# DRV8711EVM.net
KiCad netlist of a schematic drawn in Altium Designer
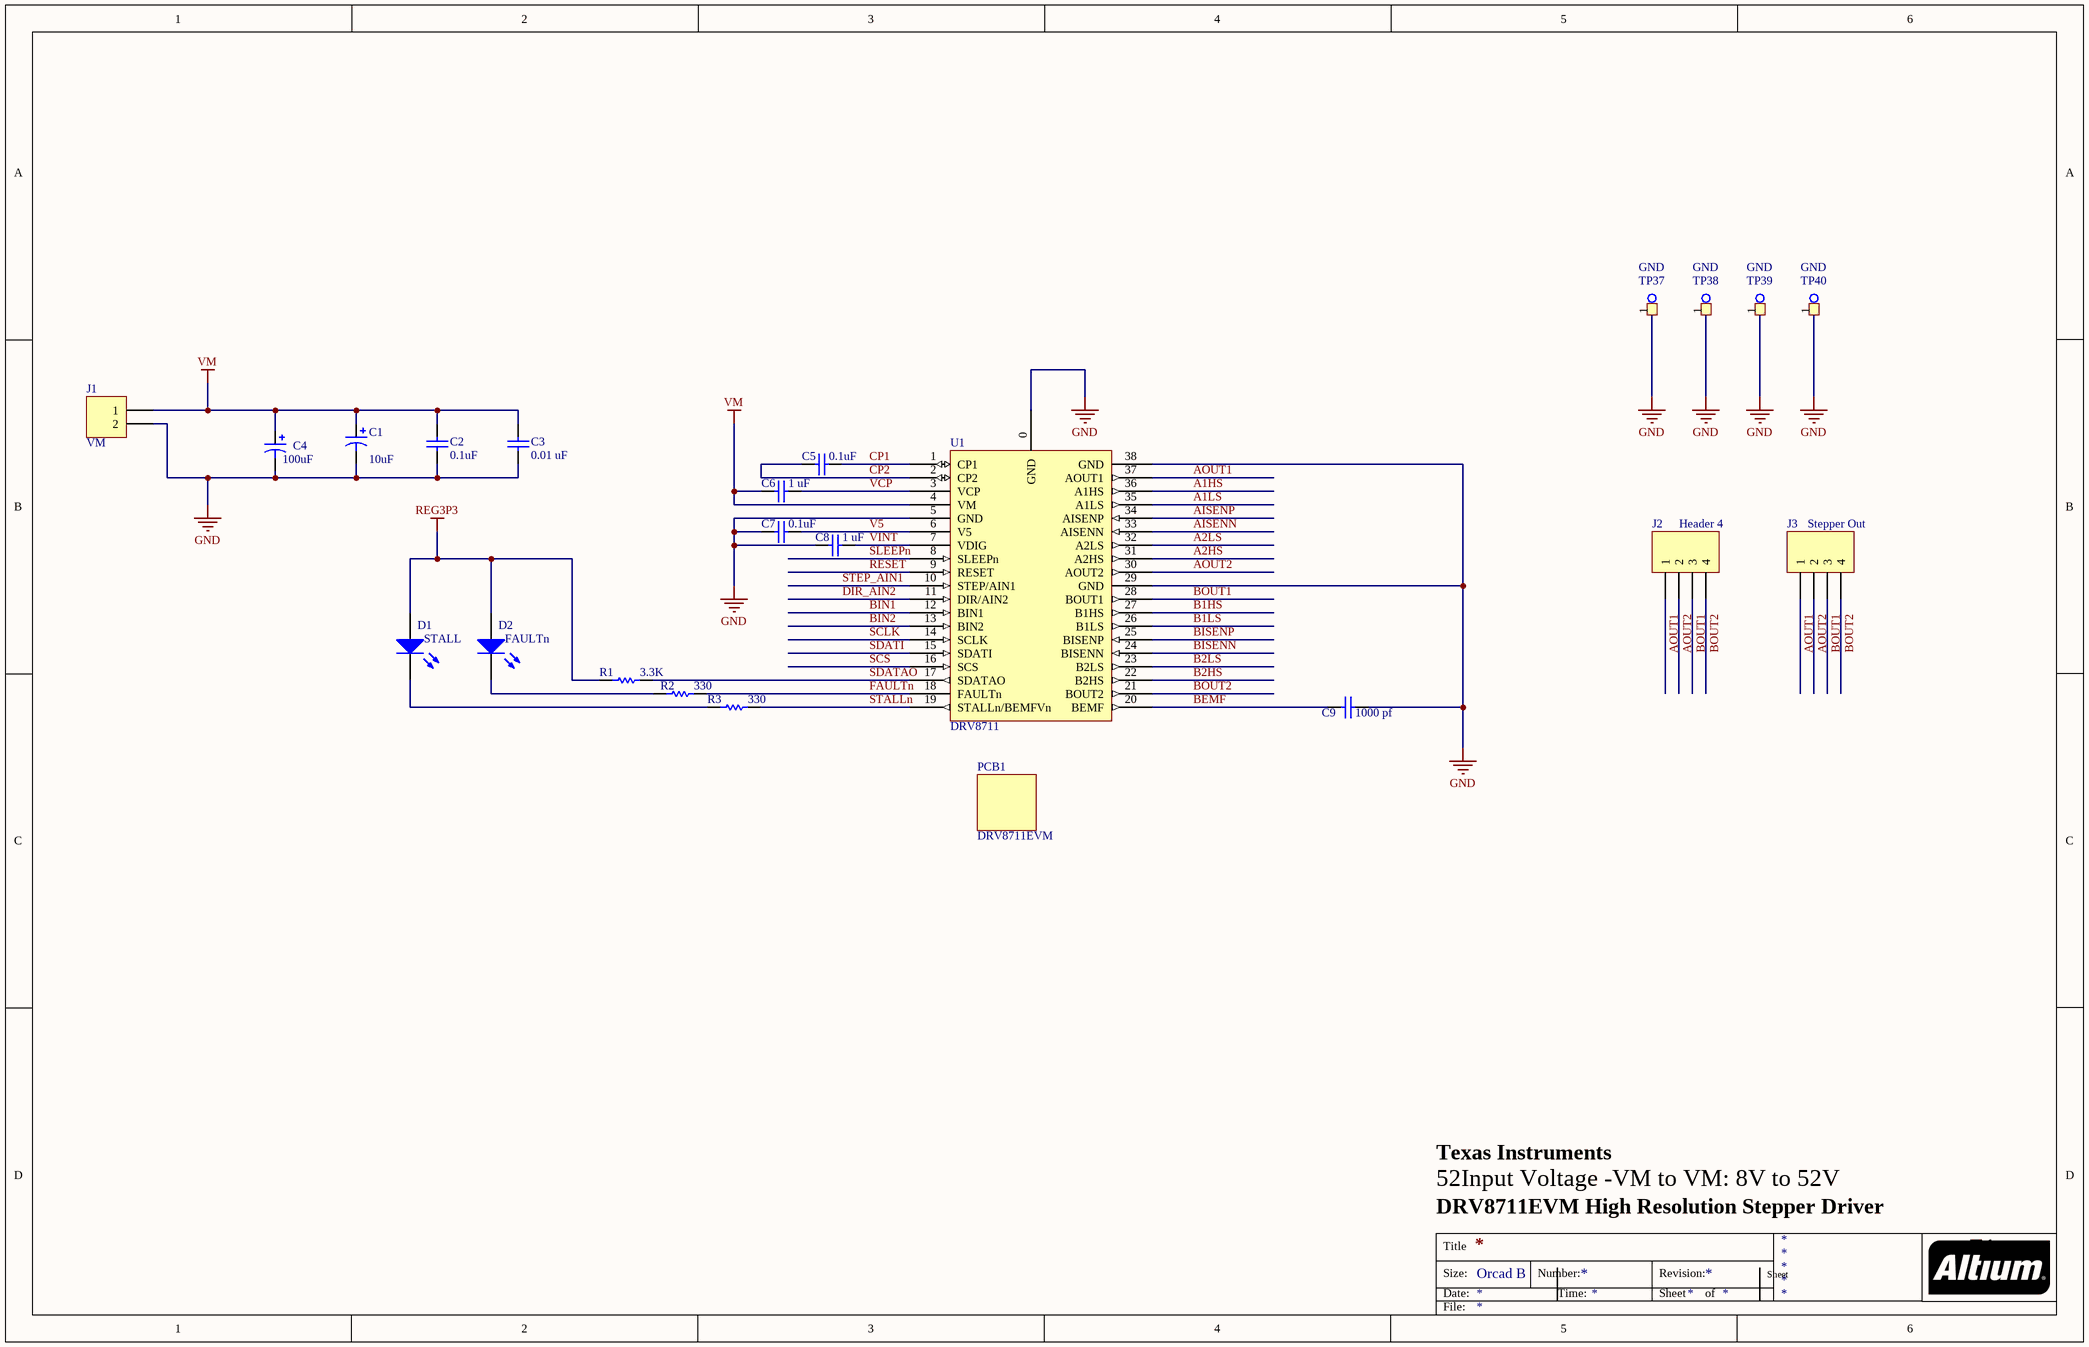
[diagram p0: DRV8711EVM.SchDoc]

(export (version "E")
  (design (tool "Eeschema 10.0.6"))
  (components
    (comp (ref "C1")
      (value "10uF")
      (footprint "RB .1/.250 - SML")
      (description "CAP ALUM 10UF 25V 20% RADIAL")
      (fields (field (name "MFG PART NUMBER") "UVR1E100MDD") (field (name "MANUFACTURER") "Nichicon"))
      (libsource (lib "Miscellaneous Devices") (part "Cap Pol1"))
    )
    (comp (ref "C2")
      (value "0.1uF")
      (footprint "0603-SMT")
      (description "Capacitor")
      (fields (field (name "MANUFACTURER") "TDK") (field (name "MFG PART NUMBER") "C1608X7S2A104M"))
      (libsource (lib "Miscellaneous Devices") (part "Cap"))
    )
    (comp (ref "C3")
      (value "0.01 uF")
      (footprint "0603-SMT")
      (description "Capacitor")
      (fields (field (name "MANUFACTURER") "TDK") (field (name "MFG PART NUMBER") "C1608X7R2A103K"))
      (libsource (lib "Miscellaneous Devices") (part "Cap"))
    )
    (comp (ref "C4")
      (value "100uF")
      (footprint "RB 5.0mm/12.5mm_NoPost")
      (description "CAP ALUM 100UF 100V 20% RADIAL")
      (fields (field (name "MFG PART NUMBER") "ECA-2AM101") (field (name "MANUFACTURER") "Panasonic"))
      (libsource (lib "Miscellaneous Devices") (part "Cap Pol1"))
    )
    (comp (ref "C5")
      (value "0.1uF")
      (footprint "0603-SMT")
      (description "Capacitor")
      (fields (field (name "MANUFACTURER") "TDK") (field (name "MFG PART NUMBER") "C1608X7S2A104M"))
      (libsource (lib "Miscellaneous Devices") (part "Cap"))
    )
    (comp (ref "C6")
      (value "1 uF")
      (footprint "1206")
      (description "Capacitor")
      (fields (field (name "MANUFACTURER") "TDK") (field (name "MFG PART NUMBER") "C3216X7R1H105K"))
      (libsource (lib "Miscellaneous Devices") (part "Cap"))
    )
    (comp (ref "C7")
      (value "0.1uF")
      (footprint "0603-SMT")
      (description "Capacitor")
      (fields (field (name "MANUFACTURER") "Yageo") (field (name "MFG PART NUMBER") "CC0603ZRY5V9BB104"))
      (libsource (lib "Miscellaneous Devices") (part "Cap"))
    )
    (comp (ref "C8")
      (value "1 uF")
      (footprint "0603-SMT")
      (description "Capacitor")
      (fields (field (name "MANUFACTURER") "TDK") (field (name "MFG PART NUMBER") "C1608Y5V1A105Z"))
      (libsource (lib "Miscellaneous Devices") (part "Cap"))
    )
    (comp (ref "C9")
      (value "1000 pf")
      (footprint "0603-SMT")
      (description "Capacitor")
      (fields (field (name "MANUFACTURER") "Yageo") (field (name "MFG PART NUMBER") "CC0603JRNPO8BN102"))
      (libsource (lib "Miscellaneous Devices") (part "Cap"))
    )
    (comp (ref "D1")
      (value "STALL")
      (footprint "1206_LED")
      (description "LED RED FACE UP 1206")
      (fields (field (name "DK PART NUMBER") "P11532CT-ND") (field (name "MANUFACTURER") "Panasonic"))
      (libsource (lib "Miscellaneous Devices") (part "LED2"))
    )
    (comp (ref "D2")
      (value "FAULTn")
      (footprint "1206_LED")
      (description "LED RED FACE UP 1206")
      (fields (field (name "DK PART NUMBER") "P11532CT-ND") (field (name "MANUFACTURER") "Panasonic"))
      (libsource (lib "Miscellaneous Devices") (part "LED2"))
    )
    (comp (ref "J1")
      (value "VM")
      (footprint "PWR_CONN2")
      (description "TERM BLOCK 5.08MM VERT 2POS PCB")
      (fields
        (field (name "MANUFACTURER") "On Shore Technologies")
        (field (name "MFG PART NUMBER") "OSTTA024163")
      )
      (libsource (lib "Miscellaneous Connectors") (part "Header 2"))
    )
    (comp (ref "J2")
      (value "Header 4")
      (footprint "PWR_CONN4")
      (description "TERM BLOCK 5.08MM VERT 4POS PCB")
      (fields
        (field (name "MANUFACTURER") "On Shore Technologies")
        (field (name "MFG PART NUMBER") "OSTTA044163")
      )
      (libsource (lib "Miscellaneous Connectors") (part "Header 4"))
    )
    (comp (ref "J3")
      (value "Stepper Out")
      (footprint "HDR1X4")
      (description "CONN HEADER .100 SNGL STR 4POS")
      (fields (field (name "DK PART NUMBER") "929647-09-04-ND") (field (name "MANUFACTURER") "3M"))
      (libsource (lib "Miscellaneous Connectors") (part "Header 4"))
    )
    (comp (ref "PCB1")
      (value "DRV8711EVM")
      (footprint "TI_LOGO")
      (description "Bare Board")
      (fields (field (name "DK PART NUMBER") "Board"))
      (libsource (lib "JIQLIB") (part "TI_LOGO"))
    )
    (comp (ref "R1")
      (value "3.3K")
      (footprint "0603-SMT")
      (description "RES 3.3K OHM 1/10W 5% 0603 SMD")
      (fields (field (name "MANUFACTURER") "Panasonic") (field (name "MFG PART NUMBER") "ERJ-3GEYJ332V"))
      (libsource (lib "Zerosen_Small") (part "Res1"))
    )
    (comp (ref "R2")
      (value "330")
      (footprint "0603-SMT")
      (description "Resistor")
      (fields (field (name "MFG PART NUMBER") "RC0603JR-07330RL") (field (name "MANUFACTURER") "Yageo"))
      (libsource (lib "Miscellaneous Devices") (part "Res1"))
    )
    (comp (ref "R3")
      (value "330")
      (footprint "0603-SMT")
      (description "Resistor")
      (fields (field (name "MFG PART NUMBER") "RC0603JR-07330RL") (field (name "MANUFACTURER") "Yageo"))
      (libsource (lib "Miscellaneous Devices") (part "Res1"))
    )
    (comp (ref "TP37")
      (value "GND")
      (footprint "TEST POINT 0.052")
      (description "TEST POINT PC COMPACT .063\"D BLK")
      (fields (field (name "MANUFACTURER") "Keystone") (field (name "MFG PART NUMBER") "5006"))
      (libsource (lib "JIQLIB") (part "TEST POINT"))
    )
    (comp (ref "TP38")
      (value "GND")
      (footprint "TEST POINT 0.052")
      (description "TEST POINT PC COMPACT .063\"D BLK")
      (fields (field (name "MANUFACTURER") "Keystone") (field (name "MFG PART NUMBER") "5006"))
      (libsource (lib "JIQLIB") (part "TEST POINT"))
    )
    (comp (ref "TP39")
      (value "GND")
      (footprint "TEST POINT 0.052")
      (description "TEST POINT PC COMPACT .063\"D BLK")
      (fields (field (name "MANUFACTURER") "Keystone") (field (name "MFG PART NUMBER") "5006"))
      (libsource (lib "JIQLIB") (part "TEST POINT"))
    )
    (comp (ref "TP40")
      (value "GND")
      (footprint "TEST POINT 0.052")
      (description "TEST POINT PC COMPACT .063\"D BLK")
      (fields (field (name "MANUFACTURER") "Keystone") (field (name "MFG PART NUMBER") "5006"))
      (libsource (lib "JIQLIB") (part "TEST POINT"))
    )
    (comp (ref "U1")
      (value "DRV8711")
      (footprint "DCP38 SMT")
      (description "Pre Driver Stepper Motor Controller")
      (fields (field (name "MANUFACTURER") "Texas Instruments") (field (name "MFG PART NUMBER") "DRV8711DCP"))
      (libsource (lib "JIQLIB") (part "DRV8711"))
    )
  )
  (nets
    (net (code "1") (name "/A1HS") (class "Default")
      (node (ref "U1") (pin "36") (pinfunction "A1HS_36") (pintype "output"))
    )
    (net (code "2") (name "/A1LS") (class "Default")
      (node (ref "U1") (pin "35") (pinfunction "A1LS_35") (pintype "output"))
    )
    (net (code "3") (name "/A2HS") (class "Default")
      (node (ref "U1") (pin "31") (pinfunction "A2HS_31") (pintype "output"))
    )
    (net (code "4") (name "/A2LS") (class "Default")
      (node (ref "U1") (pin "32") (pinfunction "A2LS_32") (pintype "output"))
    )
    (net (code "5") (name "/AISENN") (class "Default")
      (node (ref "U1") (pin "33") (pinfunction "AISENN_33") (pintype "input"))
    )
    (net (code "6") (name "/AISENP") (class "Default")
      (node (ref "U1") (pin "34") (pinfunction "AISENP_34") (pintype "input"))
    )
    (net (code "7") (name "/AOUT1") (class "Default")
      (node (ref "J2") (pin "1") (pinfunction "1_1") (pintype "passive"))
      (node (ref "J3") (pin "1") (pinfunction "1_1") (pintype "passive"))
      (node (ref "U1") (pin "37") (pinfunction "AOUT1_37") (pintype "output"))
    )
    (net (code "8") (name "/AOUT2") (class "Default")
      (node (ref "J2") (pin "2") (pinfunction "2_2") (pintype "passive"))
      (node (ref "J3") (pin "2") (pinfunction "2_2") (pintype "passive"))
      (node (ref "U1") (pin "30") (pinfunction "AOUT2_30") (pintype "output"))
    )
    (net (code "9") (name "/B1HS") (class "Default")
      (node (ref "U1") (pin "27") (pinfunction "B1HS_27") (pintype "output"))
    )
    (net (code "10") (name "/B1LS") (class "Default")
      (node (ref "U1") (pin "26") (pinfunction "B1LS_26") (pintype "output"))
    )
    (net (code "11") (name "/B2HS") (class "Default")
      (node (ref "U1") (pin "22") (pinfunction "B2HS_22") (pintype "output"))
    )
    (net (code "12") (name "/B2LS") (class "Default")
      (node (ref "U1") (pin "23") (pinfunction "B2LS_23") (pintype "output"))
    )
    (net (code "13") (name "/BEMF") (class "Default")
      (node (ref "C9") (pin "1") (pinfunction "1_1") (pintype "passive"))
      (node (ref "U1") (pin "20") (pinfunction "BEMF_20") (pintype "output"))
    )
    (net (code "14") (name "/BIN1") (class "Default")
      (node (ref "U1") (pin "12") (pinfunction "BIN1_12") (pintype "input"))
    )
    (net (code "15") (name "/BIN2") (class "Default")
      (node (ref "U1") (pin "13") (pinfunction "BIN2_13") (pintype "input"))
    )
    (net (code "16") (name "/BISENN") (class "Default")
      (node (ref "U1") (pin "24") (pinfunction "BISENN_24") (pintype "input"))
    )
    (net (code "17") (name "/BISENP") (class "Default")
      (node (ref "U1") (pin "25") (pinfunction "BISENP_25") (pintype "input"))
    )
    (net (code "18") (name "/BOUT1") (class "Default")
      (node (ref "J2") (pin "3") (pinfunction "3_3") (pintype "passive"))
      (node (ref "J3") (pin "3") (pinfunction "3_3") (pintype "passive"))
      (node (ref "U1") (pin "28") (pinfunction "BOUT1_28") (pintype "output"))
    )
    (net (code "19") (name "/BOUT2") (class "Default")
      (node (ref "J2") (pin "4") (pinfunction "4_4") (pintype "passive"))
      (node (ref "J3") (pin "4") (pinfunction "4_4") (pintype "passive"))
      (node (ref "U1") (pin "21") (pinfunction "BOUT2_21") (pintype "output"))
    )
    (net (code "20") (name "/CP1") (class "Default")
      (node (ref "C5") (pin "1") (pinfunction "1_1") (pintype "passive"))
      (node (ref "U1") (pin "1") (pinfunction "CP1_1") (pintype "bidirectional"))
    )
    (net (code "21") (name "/CP2") (class "Default")
      (node (ref "C5") (pin "2") (pinfunction "2_2") (pintype "passive"))
      (node (ref "U1") (pin "2") (pinfunction "CP2_2") (pintype "bidirectional"))
    )
    (net (code "22") (name "/DIR_AIN2") (class "Default")
      (node (ref "U1") (pin "11") (pinfunction "DIR/AIN2_11") (pintype "input"))
    )
    (net (code "23") (name "/FAULTn") (class "Default")
      (node (ref "R2") (pin "1") (pinfunction "1_1") (pintype "passive"))
      (node (ref "U1") (pin "18") (pinfunction "FAULTn_18") (pintype "open_collector"))
    )
    (net (code "24") (name "/RESET") (class "Default")
      (node (ref "U1") (pin "9") (pinfunction "RESET_9") (pintype "input"))
    )
    (net (code "25") (name "/SCLK") (class "Default")
      (node (ref "U1") (pin "14") (pinfunction "SCLK_14") (pintype "input"))
    )
    (net (code "26") (name "/SCS") (class "Default")
      (node (ref "U1") (pin "16") (pinfunction "SCS_16") (pintype "input"))
    )
    (net (code "27") (name "/SDATAO") (class "Default")
      (node (ref "R1") (pin "1") (pinfunction "1_1") (pintype "passive"))
      (node (ref "U1") (pin "17") (pinfunction "SDATAO_17") (pintype "output"))
    )
    (net (code "28") (name "/SDATI") (class "Default")
      (node (ref "U1") (pin "15") (pinfunction "SDATI_15") (pintype "input"))
    )
    (net (code "29") (name "/SLEEPn") (class "Default")
      (node (ref "U1") (pin "8") (pinfunction "SLEEPn_8") (pintype "input"))
    )
    (net (code "30") (name "/STALLn") (class "Default")
      (node (ref "R3") (pin "1") (pinfunction "1_1") (pintype "passive"))
      (node (ref "U1") (pin "19") (pinfunction "STALLn/BEMFVn_19") (pintype "output"))
    )
    (net (code "31") (name "/STEP_AIN1") (class "Default")
      (node (ref "U1") (pin "10") (pinfunction "STEP/AIN1_10") (pintype "input"))
    )
    (net (code "32") (name "/V5") (class "Default")
      (node (ref "C7") (pin "1") (pinfunction "1_1") (pintype "passive"))
      (node (ref "U1") (pin "6") (pinfunction "V5_6") (pintype "power_in"))
    )
    (net (code "33") (name "/VCP") (class "Default")
      (node (ref "C6") (pin "1") (pinfunction "1_1") (pintype "passive"))
      (node (ref "U1") (pin "3") (pinfunction "VCP_3") (pintype "power_in"))
    )
    (net (code "34") (name "/VINT") (class "Default")
      (node (ref "C8") (pin "1") (pinfunction "1_1") (pintype "passive"))
      (node (ref "U1") (pin "7") (pinfunction "VDIG_7") (pintype "power_in"))
    )
    (net (code "35") (name "GND") (class "Default")
      (node (ref "C1") (pin "2") (pinfunction "2_2") (pintype "passive"))
      (node (ref "C2") (pin "2") (pinfunction "2_2") (pintype "passive"))
      (node (ref "C3") (pin "2") (pinfunction "2_2") (pintype "passive"))
      (node (ref "C4") (pin "2") (pinfunction "2_2") (pintype "passive"))
      (node (ref "C7") (pin "2") (pinfunction "2_2") (pintype "passive"))
      (node (ref "C8") (pin "2") (pinfunction "2_2") (pintype "passive"))
      (node (ref "C9") (pin "2") (pinfunction "2_2") (pintype "passive"))
      (node (ref "J1") (pin "2") (pinfunction "2_2") (pintype "passive"))
      (node (ref "TP37") (pin "1") (pinfunction "1_1") (pintype "passive"))
      (node (ref "TP38") (pin "1") (pinfunction "1_1") (pintype "passive"))
      (node (ref "TP39") (pin "1") (pinfunction "1_1") (pintype "passive"))
      (node (ref "TP40") (pin "1") (pinfunction "1_1") (pintype "passive"))
      (node (ref "U1") (pin "0") (pinfunction "GND_0") (pintype "power_in"))
      (node (ref "U1") (pin "29") (pinfunction "GND_29") (pintype "power_in"))
      (node (ref "U1") (pin "38") (pinfunction "GND_38") (pintype "power_in"))
      (node (ref "U1") (pin "5") (pinfunction "GND_5") (pintype "power_in"))
    )
    (net (code "36") (name "Net-(D1-K)") (class "Default")
      (node (ref "D1") (pin "2") (pinfunction "K_2") (pintype "passive"))
      (node (ref "R3") (pin "2") (pinfunction "2_2") (pintype "passive"))
    )
    (net (code "37") (name "Net-(D2-K)") (class "Default")
      (node (ref "D2") (pin "2") (pinfunction "K_2") (pintype "passive"))
      (node (ref "R2") (pin "2") (pinfunction "2_2") (pintype "passive"))
    )
    (net (code "38") (name "REG3P3") (class "Default")
      (node (ref "D1") (pin "1") (pinfunction "A_1") (pintype "passive"))
      (node (ref "D2") (pin "1") (pinfunction "A_1") (pintype "passive"))
      (node (ref "R1") (pin "2") (pinfunction "2_2") (pintype "passive"))
    )
    (net (code "39") (name "VM") (class "Default")
      (node (ref "C1") (pin "1") (pinfunction "1_1") (pintype "passive"))
      (node (ref "C2") (pin "1") (pinfunction "1_1") (pintype "passive"))
      (node (ref "C3") (pin "1") (pinfunction "1_1") (pintype "passive"))
      (node (ref "C4") (pin "1") (pinfunction "1_1") (pintype "passive"))
      (node (ref "C6") (pin "2") (pinfunction "2_2") (pintype "passive"))
      (node (ref "J1") (pin "1") (pinfunction "1_1") (pintype "passive"))
      (node (ref "U1") (pin "4") (pinfunction "VM_4") (pintype "power_in"))
    )
  )
)
